# STM_bluepill_EasyEDA_file.net
KiCad netlist of a schematic drawn in EasyEDA
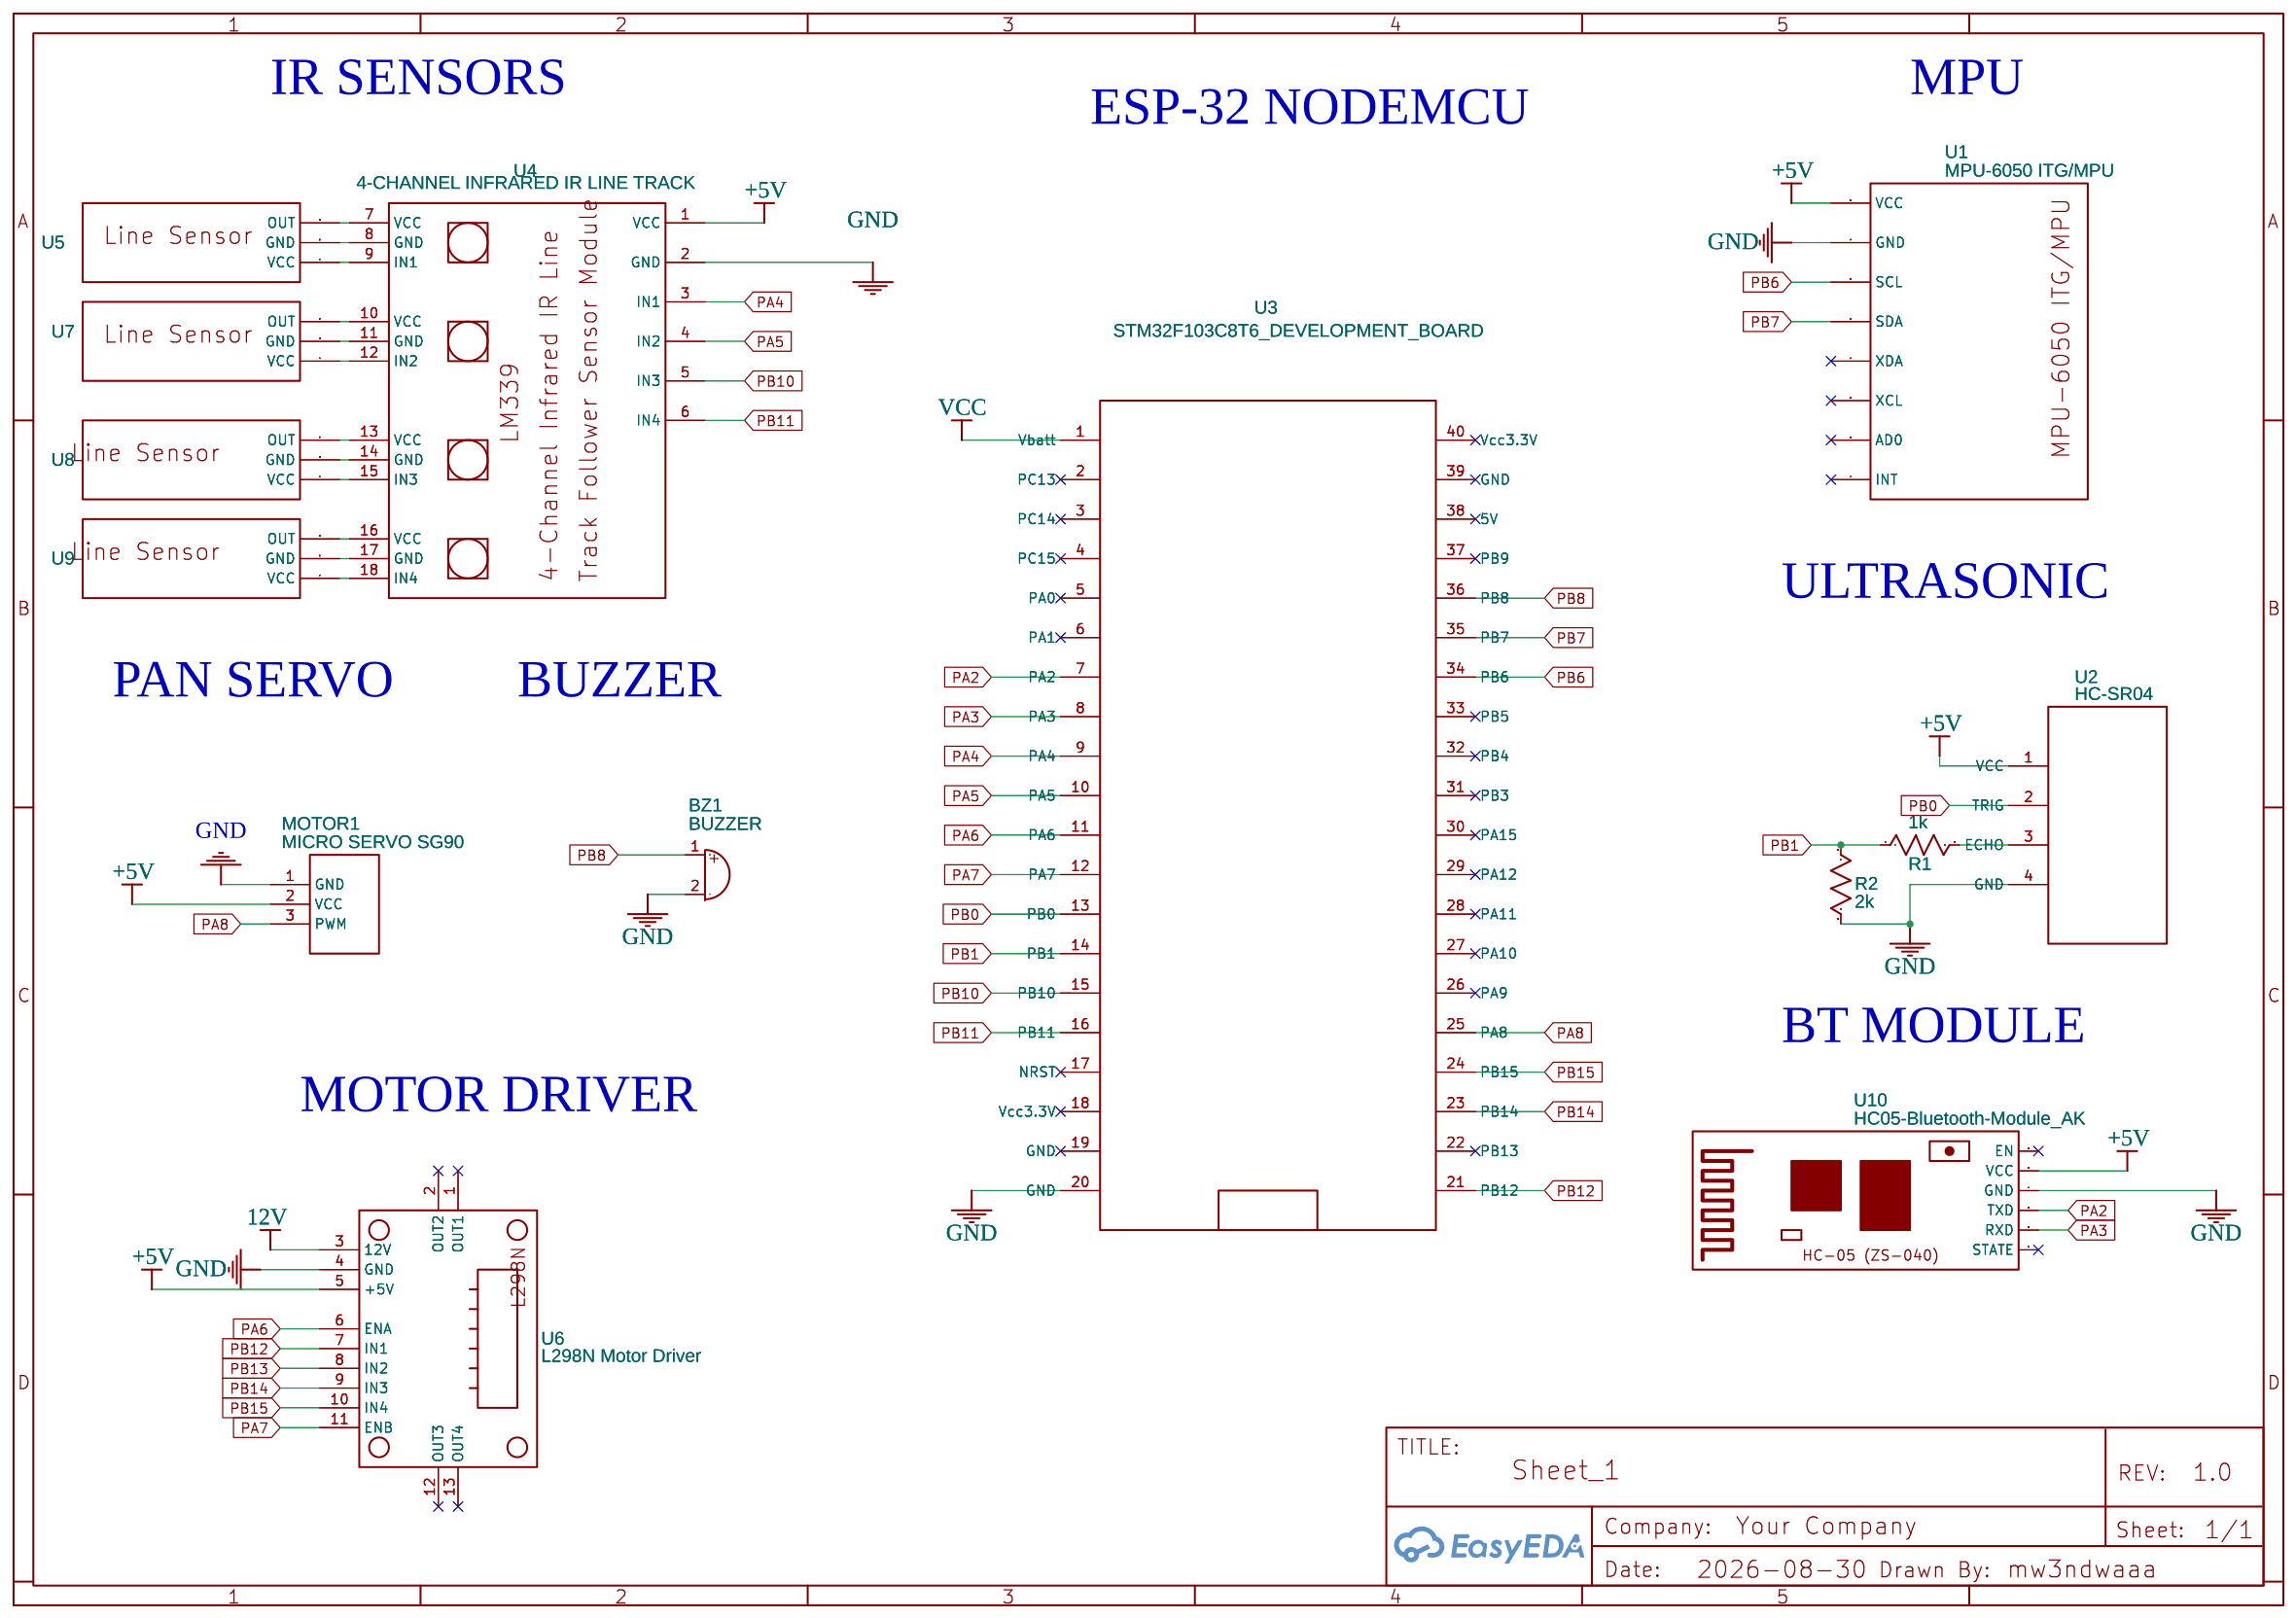
[diagram p0: schematic sheet]

(export (version "E")
  (design (tool "Eeschema 10.0.6"))
  (components
    (comp (ref "BZ1") (value "BUZZER") (libsource (lib "") (part "Device_Buzzer")))
    (comp (ref "MOTOR1") (value "MICRO SERVO SG90") (libsource (lib "") (part "MICRO SERVO SG90")))
    (comp (ref "R1") (value "1k") (libsource (lib "") (part "R_0603_US")))
    (comp (ref "R2") (value "2k") (libsource (lib "") (part "R_0603_US_1")))
    (comp (ref "U1") (value "MPU-6050 ITG/MPU") (libsource (lib "") (part "MPU-6050 ITG/MPU")))
    (comp (ref "U2") (value "HC-SR04") (libsource (lib "") (part "HC-SR04")))
    (comp (ref "U3")
      (value "STM32F103C8T6_DEVELOPMENT_BOARD")
      (fields (field (name "Manufacturer Part") "STM32Duino"))
      (libsource (lib "") (part "STM32F103C8T6_DEVELOPMENT_BOARD COPY COPY"))
    )
    (comp (ref "U4")
      (value "4-CHANNEL INFRARED IR LINE TRACK")
      (fields (field (name "Manufacturer Part") "LM339"))
      (libsource (lib "") (part "4-CHANNEL INFRARED IR LINE TRACK FOLLOWER SENSOR MODULE (LM339) COPY"))
    )
    (comp (ref "U5")
      (value "MH-Sensor-Series Line Sensor")
      (libsource (lib "") (part "MH-Sensor-Series Line Sensor"))
    )
    (comp (ref "U6") (value "L298N Motor Driver") (libsource (lib "") (part "L298N Motor Driver")))
    (comp (ref "U7")
      (value "MH-Sensor-Series Line Sensor")
      (libsource (lib "") (part "MH-Sensor-Series Line Sensor"))
    )
    (comp (ref "U8")
      (value "MH-Sensor-Series Line Sensor")
      (libsource (lib "") (part "MH-Sensor-Series Line Sensor_1"))
    )
    (comp (ref "U9")
      (value "MH-Sensor-Series Line Sensor")
      (libsource (lib "") (part "MH-Sensor-Series Line Sensor_1"))
    )
    (comp (ref "U10")
      (value "HC05-Bluetooth-Module_AK")
      (libsource (lib "") (part "HC05-Bluetooth-Module_AK"))
    )
  )
  (nets
    (net (code "1") (name "+5V") (class "Default")
      (node (ref "MOTOR1") (pin "2") (pinfunction "VCC_2") (pintype "unspecified"))
      (node (ref "U1") (pin "0") (pinfunction "VCC_0") (pintype "unspecified"))
      (node (ref "U10") (pin "5") (pinfunction "VCC_5") (pintype "output"))
      (node (ref "U4") (pin "1") (pinfunction "VCC_1") (pintype "unspecified"))
      (node (ref "U6") (pin "5") (pinfunction "+5V_5") (pintype "unspecified"))
    )
    (net (code "2") (name "12V") (class "Default")
      (node (ref "U6") (pin "3") (pinfunction "12V_3") (pintype "unspecified"))
    )
    (net (code "3") (name "GND") (class "Default")
      (node (ref "BZ1") (pin "2") (pinfunction "-_2") (pintype "unspecified"))
      (node (ref "MOTOR1") (pin "1") (pinfunction "GND_1") (pintype "unspecified"))
      (node (ref "R2") (pin "2") (pinfunction "2_2") (pintype "unspecified"))
      (node (ref "U1") (pin "1") (pinfunction "GND_1") (pintype "unspecified"))
      (node (ref "U10") (pin "4") (pinfunction "GND_4") (pintype "input"))
      (node (ref "U4") (pin "2") (pinfunction "GND_2") (pintype "unspecified"))
      (node (ref "U6") (pin "4") (pinfunction "GND_4") (pintype "unspecified"))
    )
    (net (code "4") (name "Net-(U5-GND)") (class "Default")
      (node (ref "U4") (pin "8") (pinfunction "GND_8") (pintype "unspecified"))
      (node (ref "U5") (pin "3") (pinfunction "GND_3") (pintype "passive"))
    )
    (net (code "5") (name "Net-(U5-OUT)") (class "Default")
      (node (ref "U4") (pin "7") (pinfunction "VCC_7") (pintype "unspecified"))
      (node (ref "U5") (pin "2") (pinfunction "OUT_2") (pintype "unspecified"))
    )
    (net (code "6") (name "Net-(U5-VCC)") (class "Default")
      (node (ref "U4") (pin "9") (pinfunction "IN1_9") (pintype "unspecified"))
      (node (ref "U5") (pin "4") (pinfunction "VCC_4") (pintype "passive"))
    )
    (net (code "7") (name "Net-(U7-GND)") (class "Default")
      (node (ref "U4") (pin "11") (pinfunction "GND_11") (pintype "unspecified"))
      (node (ref "U7") (pin "3") (pinfunction "GND_3") (pintype "passive"))
    )
    (net (code "8") (name "Net-(U7-OUT)") (class "Default")
      (node (ref "U4") (pin "10") (pinfunction "VCC_10") (pintype "unspecified"))
      (node (ref "U7") (pin "2") (pinfunction "OUT_2") (pintype "unspecified"))
    )
    (net (code "9") (name "Net-(U7-VCC)") (class "Default")
      (node (ref "U4") (pin "12") (pinfunction "IN2_12") (pintype "unspecified"))
      (node (ref "U7") (pin "4") (pinfunction "VCC_4") (pintype "passive"))
    )
    (net (code "10") (name "Net-(U8-GND)") (class "Default")
      (node (ref "U4") (pin "14") (pinfunction "GND_14") (pintype "unspecified"))
      (node (ref "U8") (pin "3") (pinfunction "GND_3") (pintype "passive"))
    )
    (net (code "11") (name "Net-(U8-OUT)") (class "Default")
      (node (ref "U4") (pin "13") (pinfunction "VCC_13") (pintype "unspecified"))
      (node (ref "U8") (pin "2") (pinfunction "OUT_2") (pintype "unspecified"))
    )
    (net (code "12") (name "Net-(U8-VCC)") (class "Default")
      (node (ref "U4") (pin "15") (pinfunction "IN3_15") (pintype "unspecified"))
      (node (ref "U8") (pin "4") (pinfunction "VCC_4") (pintype "passive"))
    )
    (net (code "13") (name "Net-(U9-GND)") (class "Default")
      (node (ref "U4") (pin "17") (pinfunction "GND_17") (pintype "unspecified"))
      (node (ref "U9") (pin "3") (pinfunction "GND_3") (pintype "passive"))
    )
    (net (code "14") (name "Net-(U9-OUT)") (class "Default")
      (node (ref "U4") (pin "16") (pinfunction "VCC_16") (pintype "unspecified"))
      (node (ref "U9") (pin "2") (pinfunction "OUT_2") (pintype "unspecified"))
    )
    (net (code "15") (name "Net-(U9-VCC)") (class "Default")
      (node (ref "U4") (pin "18") (pinfunction "IN4_18") (pintype "unspecified"))
      (node (ref "U9") (pin "4") (pinfunction "VCC_4") (pintype "passive"))
    )
    (net (code "16") (name "PA2") (class "Default")
      (node (ref "U10") (pin "3") (pinfunction "TXD_3") (pintype "passive"))
    )
    (net (code "17") (name "PA3") (class "Default")
      (node (ref "U10") (pin "2") (pinfunction "RXD_2") (pintype "passive"))
    )
    (net (code "18") (name "PA4") (class "Default")
      (node (ref "U4") (pin "3") (pinfunction "IN1_3") (pintype "unspecified"))
    )
    (net (code "19") (name "PA5") (class "Default")
      (node (ref "U4") (pin "4") (pinfunction "IN2_4") (pintype "unspecified"))
    )
    (net (code "20") (name "PA6") (class "Default")
      (node (ref "U6") (pin "6") (pinfunction "ENA_6") (pintype "unspecified"))
    )
    (net (code "21") (name "PA7") (class "Default")
      (node (ref "U6") (pin "11") (pinfunction "ENB_11") (pintype "unspecified"))
    )
    (net (code "22") (name "PA8") (class "Default")
      (node (ref "MOTOR1") (pin "3") (pinfunction "PWM_3") (pintype "unspecified"))
    )
    (net (code "24") (name "PB1") (class "Default")
      (node (ref "R1") (pin "1") (pinfunction "1_1") (pintype "unspecified"))
      (node (ref "R2") (pin "1") (pinfunction "1_1") (pintype "unspecified"))
    )
    (net (code "25") (name "PB6") (class "Default")
      (node (ref "U1") (pin "2") (pinfunction "SCL_2") (pintype "unspecified"))
    )
    (net (code "26") (name "PB7") (class "Default")
      (node (ref "U1") (pin "3") (pinfunction "SDA_3") (pintype "unspecified"))
    )
    (net (code "27") (name "PB8") (class "Default")
      (node (ref "BZ1") (pin "1") (pinfunction "+_1") (pintype "unspecified"))
    )
    (net (code "28") (name "PB10") (class "Default")
      (node (ref "U4") (pin "5") (pinfunction "IN3_5") (pintype "unspecified"))
    )
    (net (code "29") (name "PB11") (class "Default")
      (node (ref "U4") (pin "6") (pinfunction "IN4_6") (pintype "unspecified"))
    )
    (net (code "30") (name "PB12") (class "Default")
      (node (ref "U6") (pin "7") (pinfunction "IN1_7") (pintype "unspecified"))
    )
    (net (code "31") (name "PB13") (class "Default")
      (node (ref "U6") (pin "8") (pinfunction "IN2_8") (pintype "unspecified"))
    )
    (net (code "32") (name "PB14") (class "Default")
      (node (ref "U6") (pin "9") (pinfunction "IN3_9") (pintype "unspecified"))
    )
    (net (code "33") (name "PB15") (class "Default")
      (node (ref "U6") (pin "10") (pinfunction "IN4_10") (pintype "unspecified"))
    )
    (net (code "35") (name "unconnected-(R1-Pad2)") (class "Default")
      (node (ref "R1") (pin "2") (pinfunction "2_2") (pintype "unspecified"))
    )
    (net (code "36") (name "unconnected-(U1-AD0-Pad6)") (class "Default")
      (node (ref "U1") (pin "6") (pinfunction "AD0_6") (pintype "unspecified+no_connect"))
    )
    (net (code "37") (name "unconnected-(U1-INT-Pad7)") (class "Default")
      (node (ref "U1") (pin "7") (pinfunction "INT_7") (pintype "unspecified+no_connect"))
    )
    (net (code "38") (name "unconnected-(U1-XCL-Pad5)") (class "Default")
      (node (ref "U1") (pin "5") (pinfunction "XCL_5") (pintype "unspecified+no_connect"))
    )
    (net (code "39") (name "unconnected-(U1-XDA-Pad4)") (class "Default")
      (node (ref "U1") (pin "4") (pinfunction "XDA_4") (pintype "unspecified+no_connect"))
    )
    (net (code "40") (name "unconnected-(U2-ECHO-Pad3)") (class "Default")
      (node (ref "U2") (pin "3") (pinfunction "ECHO_3") (pintype "unspecified"))
    )
    (net (code "41") (name "unconnected-(U2-GND-Pad4)") (class "Default")
      (node (ref "U2") (pin "4") (pinfunction "GND_4") (pintype "unspecified"))
    )
    (net (code "42") (name "unconnected-(U2-TRIG-Pad2)") (class "Default")
      (node (ref "U2") (pin "2") (pinfunction "TRIG_2") (pintype "unspecified"))
    )
    (net (code "43") (name "unconnected-(U2-VCC-Pad1)") (class "Default")
      (node (ref "U2") (pin "1") (pinfunction "VCC_1") (pintype "unspecified"))
    )
    (net (code "44") (name "unconnected-(U3-5V-Pad38)") (class "Default")
      (node (ref "U3") (pin "38") (pinfunction "5V_38") (pintype "unspecified"))
    )
    (net (code "45") (name "unconnected-(U3-GND-Pad19)") (class "Default")
      (node (ref "U3") (pin "19") (pinfunction "GND_19") (pintype "unspecified"))
    )
    (net (code "46") (name "unconnected-(U3-GND-Pad20)") (class "Default")
      (node (ref "U3") (pin "20") (pinfunction "GND_20") (pintype "unspecified"))
    )
    (net (code "47") (name "unconnected-(U3-GND-Pad39)") (class "Default")
      (node (ref "U3") (pin "39") (pinfunction "GND_39") (pintype "unspecified"))
    )
    (net (code "48") (name "unconnected-(U3-NRST-Pad17)") (class "Default")
      (node (ref "U3") (pin "17") (pinfunction "NRST_17") (pintype "unspecified"))
    )
    (net (code "49") (name "unconnected-(U3-PA0-Pad5)") (class "Default")
      (node (ref "U3") (pin "5") (pinfunction "PA0_5") (pintype "unspecified"))
    )
    (net (code "50") (name "unconnected-(U3-PA1-Pad6)") (class "Default")
      (node (ref "U3") (pin "6") (pinfunction "PA1_6") (pintype "unspecified"))
    )
    (net (code "51") (name "unconnected-(U3-PA2-Pad7)") (class "Default")
      (node (ref "U3") (pin "7") (pinfunction "PA2_7") (pintype "unspecified"))
    )
    (net (code "52") (name "unconnected-(U3-PA3-Pad8)") (class "Default")
      (node (ref "U3") (pin "8") (pinfunction "PA3_8") (pintype "unspecified"))
    )
    (net (code "53") (name "unconnected-(U3-PA4-Pad9)") (class "Default")
      (node (ref "U3") (pin "9") (pinfunction "PA4_9") (pintype "unspecified"))
    )
    (net (code "54") (name "unconnected-(U3-PA5-Pad10)") (class "Default")
      (node (ref "U3") (pin "10") (pinfunction "PA5_10") (pintype "unspecified"))
    )
    (net (code "55") (name "unconnected-(U3-PA6-Pad11)") (class "Default")
      (node (ref "U3") (pin "11") (pinfunction "PA6_11") (pintype "unspecified"))
    )
    (net (code "56") (name "unconnected-(U3-PA7-Pad12)") (class "Default")
      (node (ref "U3") (pin "12") (pinfunction "PA7_12") (pintype "unspecified"))
    )
    (net (code "57") (name "unconnected-(U3-PA8-Pad25)") (class "Default")
      (node (ref "U3") (pin "25") (pinfunction "PA8_25") (pintype "unspecified"))
    )
    (net (code "58") (name "unconnected-(U3-PA9-Pad26)") (class "Default")
      (node (ref "U3") (pin "26") (pinfunction "PA9_26") (pintype "unspecified"))
    )
    (net (code "59") (name "unconnected-(U3-PA10-Pad27)") (class "Default")
      (node (ref "U3") (pin "27") (pinfunction "PA10_27") (pintype "unspecified"))
    )
    (net (code "60") (name "unconnected-(U3-PA11-Pad28)") (class "Default")
      (node (ref "U3") (pin "28") (pinfunction "PA11_28") (pintype "unspecified"))
    )
    (net (code "61") (name "unconnected-(U3-PA12-Pad29)") (class "Default")
      (node (ref "U3") (pin "29") (pinfunction "PA12_29") (pintype "unspecified"))
    )
    (net (code "62") (name "unconnected-(U3-PA15-Pad30)") (class "Default")
      (node (ref "U3") (pin "30") (pinfunction "PA15_30") (pintype "unspecified"))
    )
    (net (code "63") (name "unconnected-(U3-PB0-Pad13)") (class "Default")
      (node (ref "U3") (pin "13") (pinfunction "PB0_13") (pintype "unspecified"))
    )
    (net (code "64") (name "unconnected-(U3-PB1-Pad14)") (class "Default")
      (node (ref "U3") (pin "14") (pinfunction "PB1_14") (pintype "unspecified"))
    )
    (net (code "65") (name "unconnected-(U3-PB3-Pad31)") (class "Default")
      (node (ref "U3") (pin "31") (pinfunction "PB3_31") (pintype "unspecified"))
    )
    (net (code "66") (name "unconnected-(U3-PB4-Pad32)") (class "Default")
      (node (ref "U3") (pin "32") (pinfunction "PB4_32") (pintype "unspecified"))
    )
    (net (code "67") (name "unconnected-(U3-PB5-Pad33)") (class "Default")
      (node (ref "U3") (pin "33") (pinfunction "PB5_33") (pintype "unspecified"))
    )
    (net (code "68") (name "unconnected-(U3-PB6-Pad34)") (class "Default")
      (node (ref "U3") (pin "34") (pinfunction "PB6_34") (pintype "unspecified"))
    )
    (net (code "69") (name "unconnected-(U3-PB7-Pad35)") (class "Default")
      (node (ref "U3") (pin "35") (pinfunction "PB7_35") (pintype "unspecified"))
    )
    (net (code "70") (name "unconnected-(U3-PB8-Pad36)") (class "Default")
      (node (ref "U3") (pin "36") (pinfunction "PB8_36") (pintype "unspecified"))
    )
    (net (code "71") (name "unconnected-(U3-PB9-Pad37)") (class "Default")
      (node (ref "U3") (pin "37") (pinfunction "PB9_37") (pintype "unspecified"))
    )
    (net (code "72") (name "unconnected-(U3-PB10-Pad15)") (class "Default")
      (node (ref "U3") (pin "15") (pinfunction "PB10_15") (pintype "unspecified"))
    )
    (net (code "73") (name "unconnected-(U3-PB11-Pad16)") (class "Default")
      (node (ref "U3") (pin "16") (pinfunction "PB11_16") (pintype "unspecified"))
    )
    (net (code "74") (name "unconnected-(U3-PB12-Pad21)") (class "Default")
      (node (ref "U3") (pin "21") (pinfunction "PB12_21") (pintype "unspecified"))
    )
    (net (code "75") (name "unconnected-(U3-PB13-Pad22)") (class "Default")
      (node (ref "U3") (pin "22") (pinfunction "PB13_22") (pintype "unspecified"))
    )
    (net (code "76") (name "unconnected-(U3-PB14-Pad23)") (class "Default")
      (node (ref "U3") (pin "23") (pinfunction "PB14_23") (pintype "unspecified"))
    )
    (net (code "77") (name "unconnected-(U3-PB15-Pad24)") (class "Default")
      (node (ref "U3") (pin "24") (pinfunction "PB15_24") (pintype "unspecified"))
    )
    (net (code "78") (name "unconnected-(U3-PC13-Pad2)") (class "Default")
      (node (ref "U3") (pin "2") (pinfunction "PC13_2") (pintype "unspecified"))
    )
    (net (code "79") (name "unconnected-(U3-PC14-Pad3)") (class "Default")
      (node (ref "U3") (pin "3") (pinfunction "PC14_3") (pintype "unspecified"))
    )
    (net (code "80") (name "unconnected-(U3-PC15-Pad4)") (class "Default")
      (node (ref "U3") (pin "4") (pinfunction "PC15_4") (pintype "unspecified"))
    )
    (net (code "81") (name "unconnected-(U3-Vbatt-Pad1)") (class "Default")
      (node (ref "U3") (pin "1") (pinfunction "Vbatt_1") (pintype "unspecified"))
    )
    (net (code "82") (name "unconnected-(U3-Vcc3.3V-Pad18)") (class "Default")
      (node (ref "U3") (pin "18") (pinfunction "Vcc3.3V_18") (pintype "unspecified"))
    )
    (net (code "83") (name "unconnected-(U3-Vcc3.3V-Pad40)") (class "Default")
      (node (ref "U3") (pin "40") (pinfunction "Vcc3.3V_40") (pintype "unspecified"))
    )
    (net (code "84") (name "unconnected-(U6-OUT1-Pad1)") (class "Default")
      (node (ref "U6") (pin "1") (pinfunction "OUT1_1") (pintype "unspecified+no_connect"))
    )
    (net (code "85") (name "unconnected-(U6-OUT2-Pad2)") (class "Default")
      (node (ref "U6") (pin "2") (pinfunction "OUT2_2") (pintype "unspecified+no_connect"))
    )
    (net (code "86") (name "unconnected-(U6-OUT3-Pad12)") (class "Default")
      (node (ref "U6") (pin "12") (pinfunction "OUT3_12") (pintype "unspecified+no_connect"))
    )
    (net (code "87") (name "unconnected-(U6-OUT4-Pad13)") (class "Default")
      (node (ref "U6") (pin "13") (pinfunction "OUT4_13") (pintype "unspecified+no_connect"))
    )
    (net (code "88") (name "unconnected-(U10-EN-Pad6)") (class "Default")
      (node (ref "U10") (pin "6") (pinfunction "EN_6") (pintype "bidirectional+no_connect"))
    )
    (net (code "89") (name "unconnected-(U10-STATE-Pad1)") (class "Default")
      (node (ref "U10") (pin "1") (pinfunction "STATE_1") (pintype "passive+no_connect"))
    )
  )
)
